# powerblade_2v0.net
KiCad netlist of a schematic drawn in EAGLE
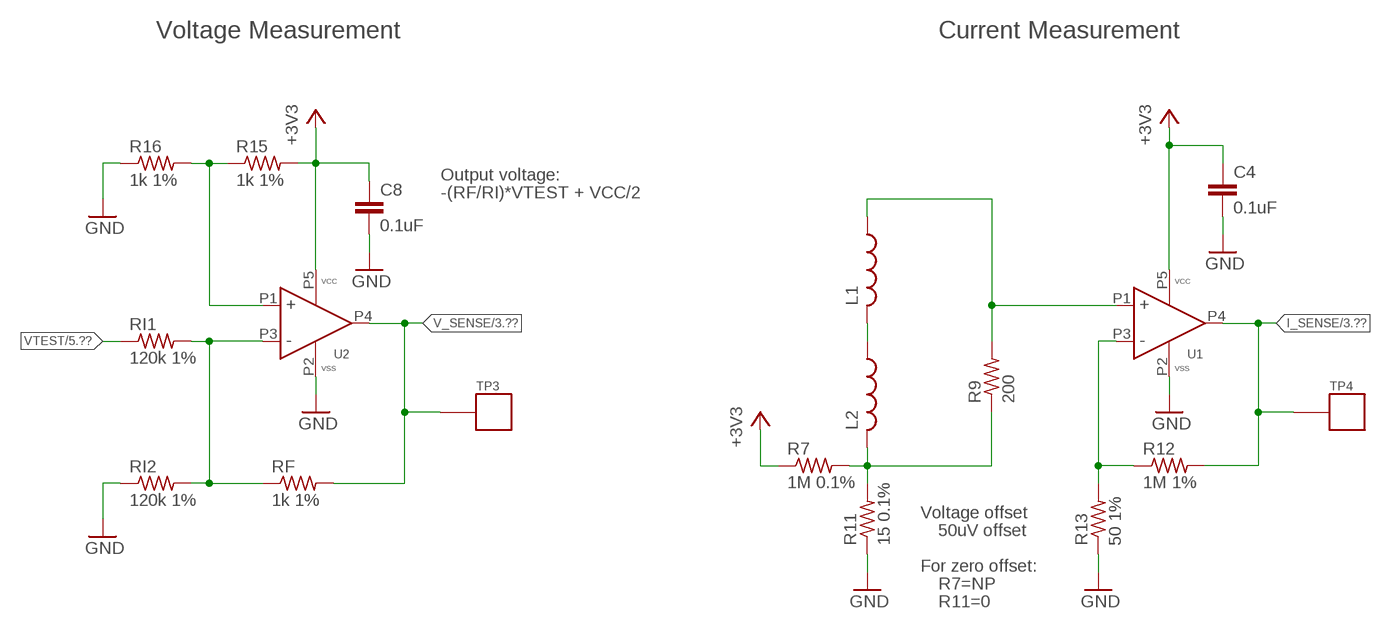
[diagram p0: schematic, sheet 1]
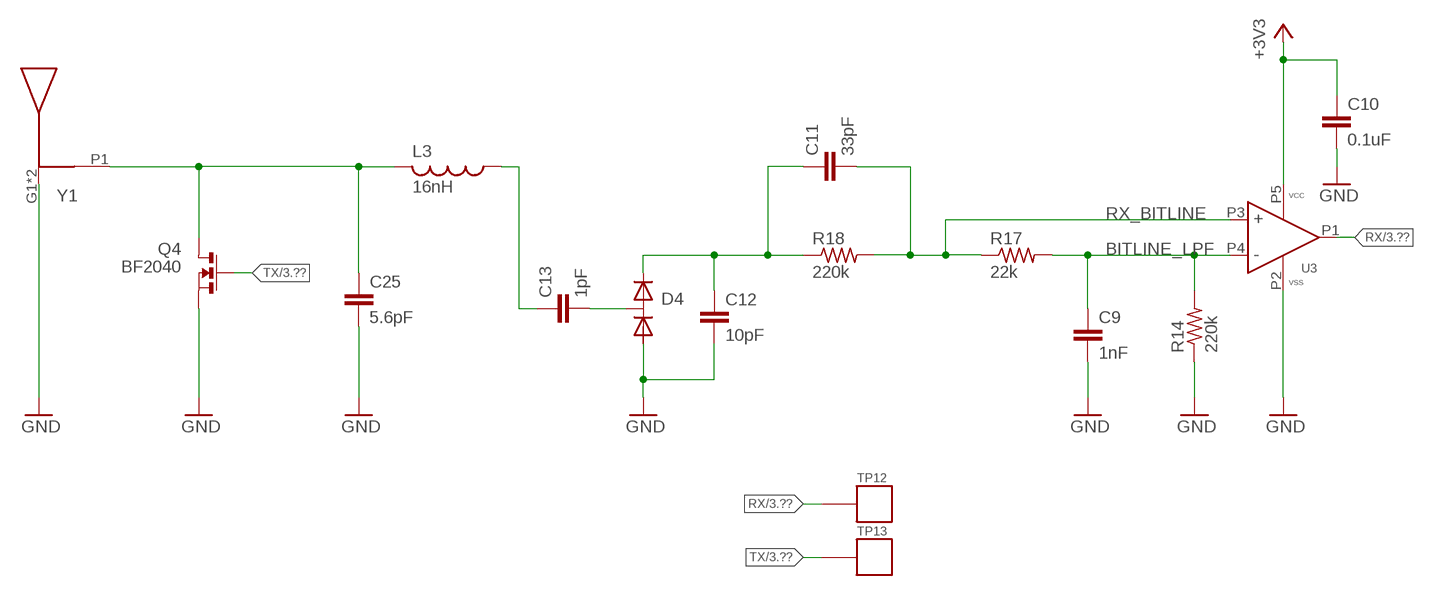
[diagram p1: schematic, sheet 2]
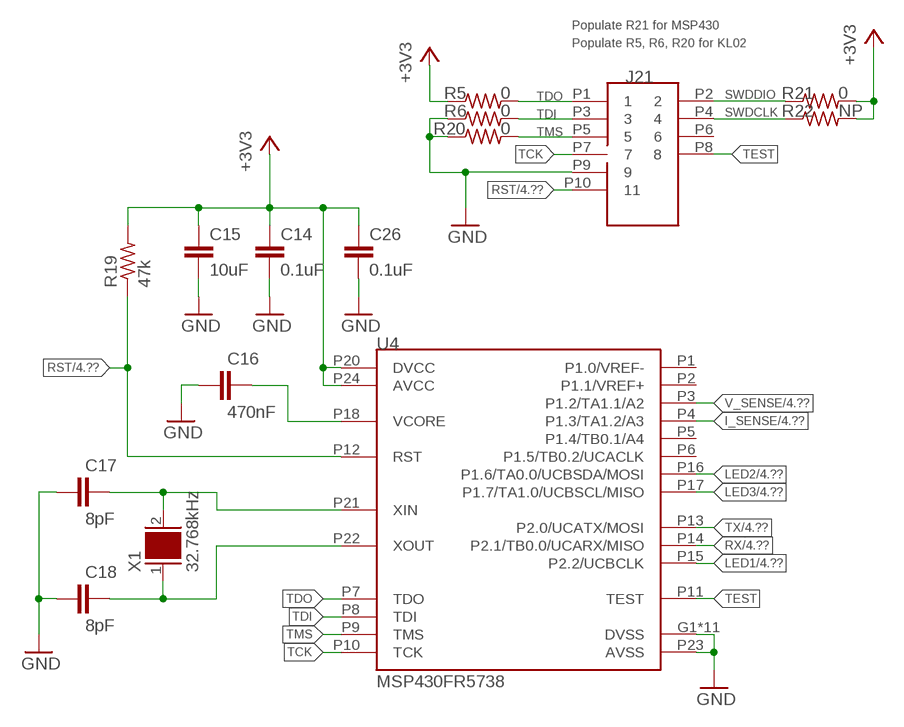
[diagram p2: schematic, sheet 3]
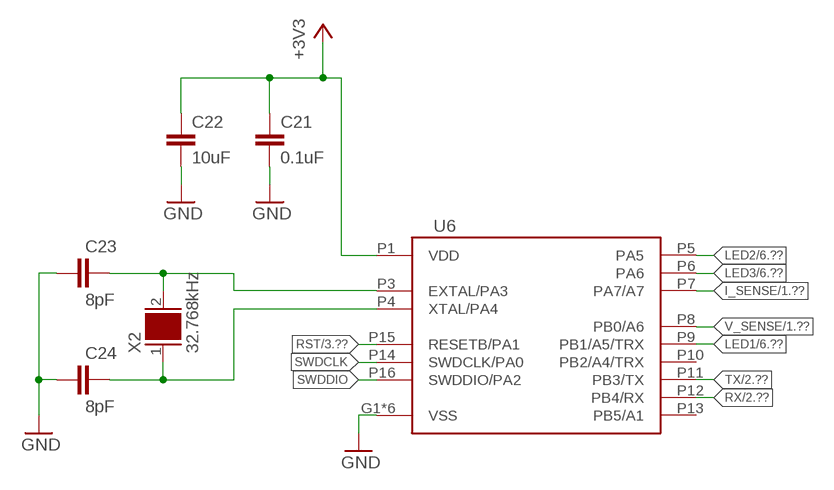
[diagram p3: schematic, sheet 4]
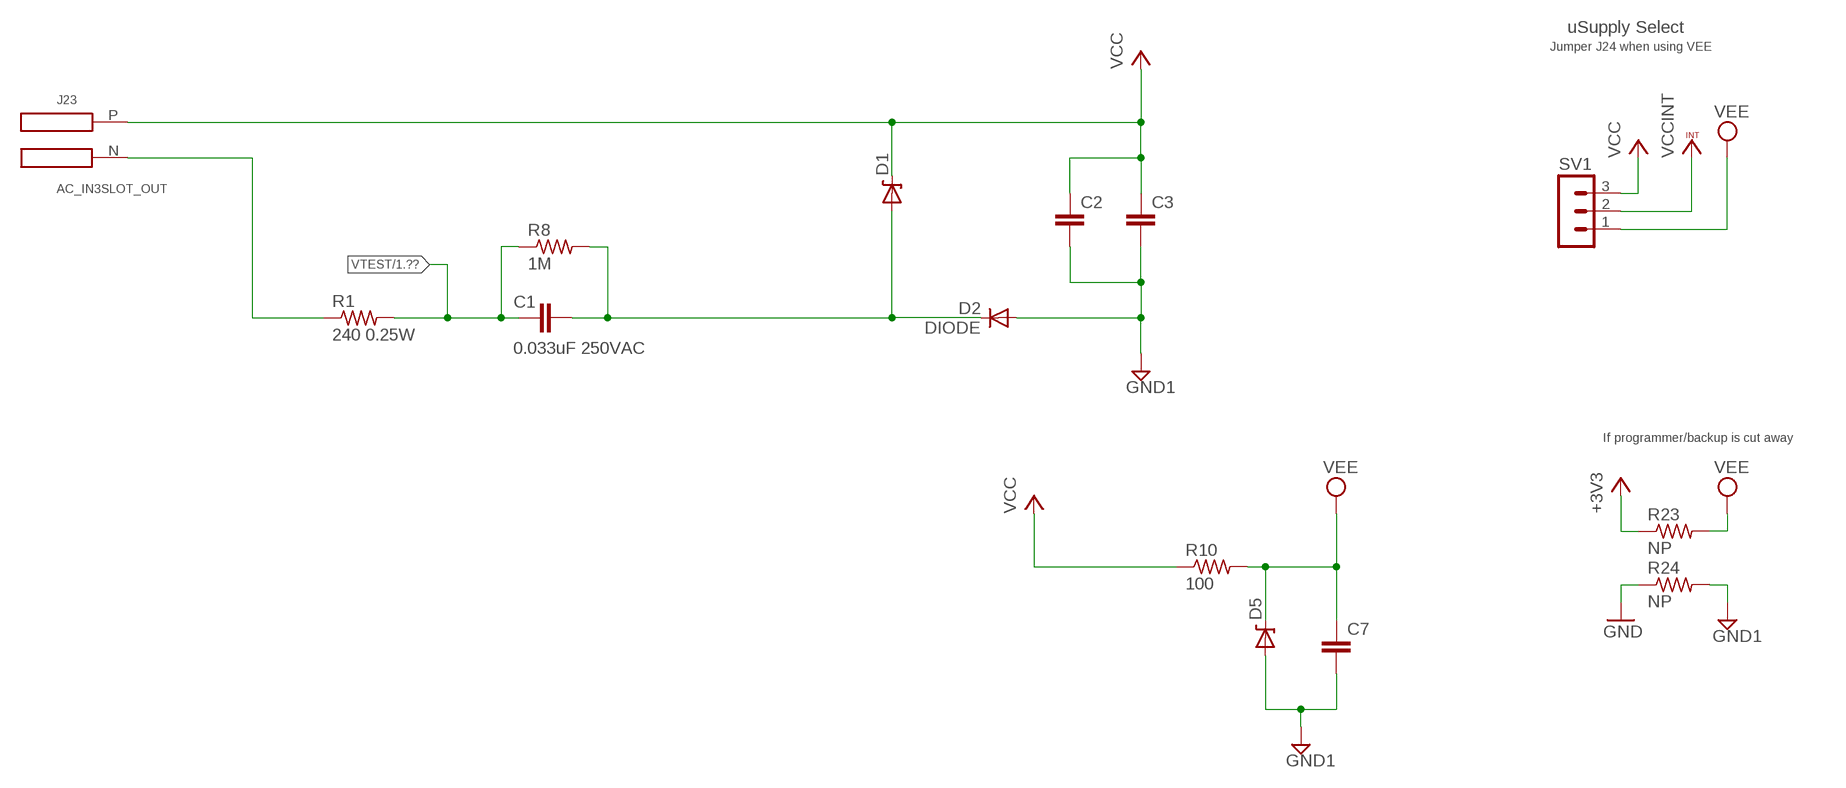
[diagram p4: schematic, sheet 5]
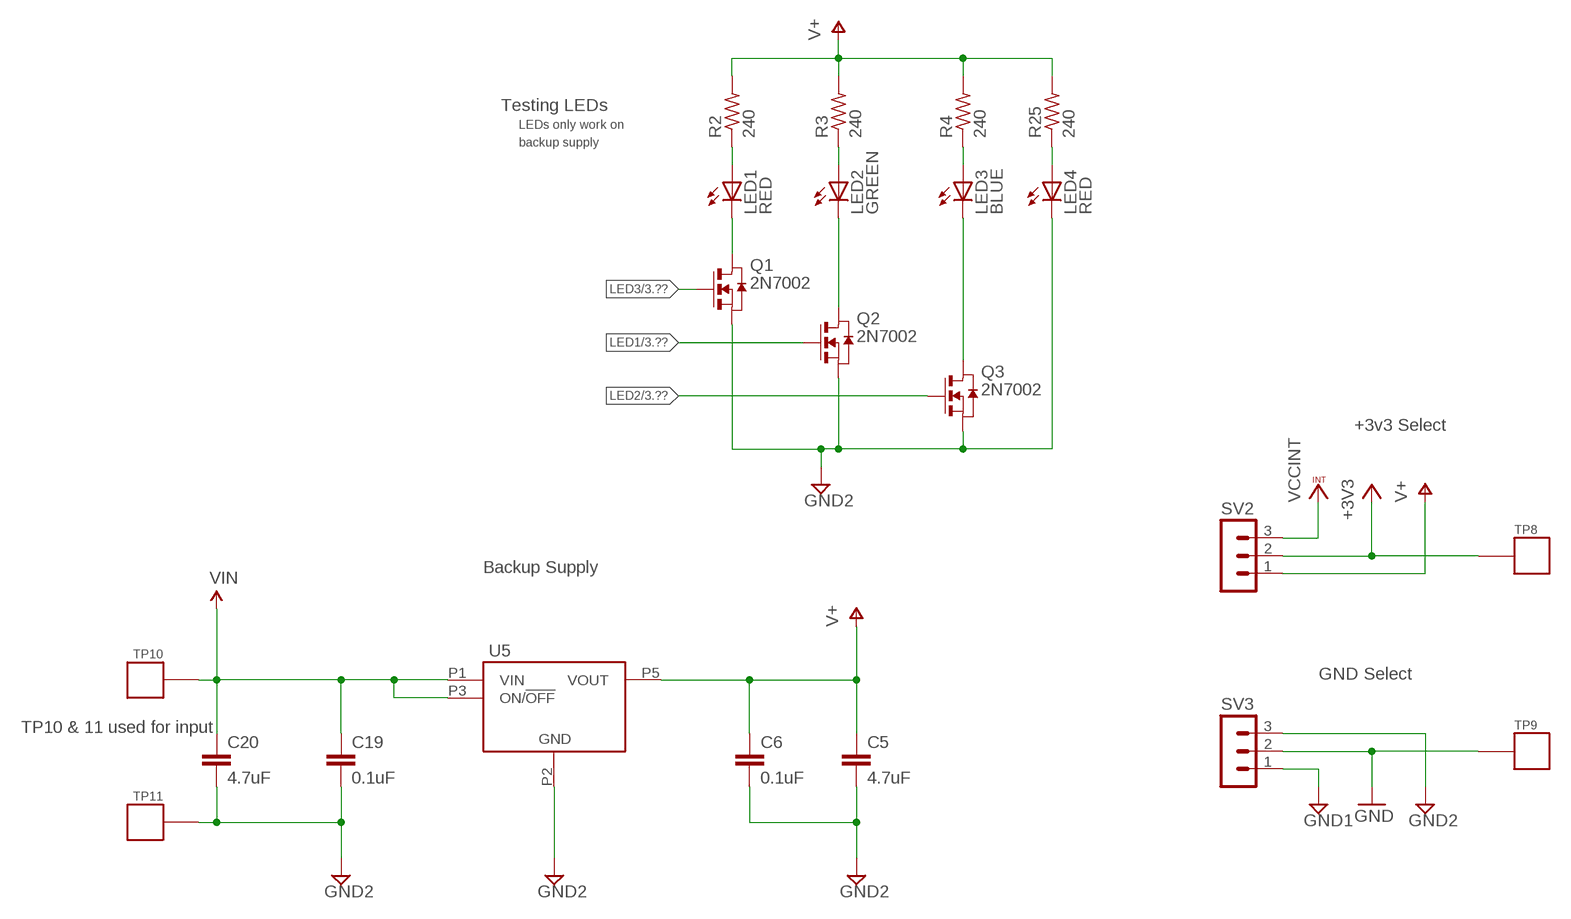
[diagram p5: schematic, sheet 6]

(export (version "E")
  (design (tool "Eeschema 10.0.6"))
  (components
    (comp (ref "C14")
      (value "0.1uF")
      (footprint "eagle-import:C0603")
      (libsource (lib "eagle-import") (part "C-EUC0603"))
    )
    (comp (ref "C15")
      (value "10uF")
      (footprint "eagle-import:C0603")
      (libsource (lib "eagle-import") (part "C-EUC0603"))
    )
    (comp (ref "C16")
      (value "470nF")
      (footprint "eagle-import:C0603")
      (libsource (lib "eagle-import") (part "C-EUC0603"))
    )
    (comp (ref "C17")
      (value "8pF")
      (footprint "eagle-import:C0603")
      (libsource (lib "eagle-import") (part "C-EUC0603"))
    )
    (comp (ref "C18")
      (value "8pF")
      (footprint "eagle-import:C0603")
      (libsource (lib "eagle-import") (part "C-EUC0603"))
    )
    (comp (ref "C26")
      (value "0.1uF")
      (footprint "eagle-import:C0603")
      (libsource (lib "eagle-import") (part "C-EUC0603"))
    )
    (comp (ref "J21")
      (value "JTAG_14PIN_IDC-NL")
      (footprint "eagle-import:TC2050-IDC-NL-430")
      (fields (field (name "TAG-CONNECT") "TC2050-IDC-NL-430"))
      (libsource (lib "eagle-import") (part "JTAG_14PIN_IDC-NL"))
    )
    (comp (ref "R5")
      (value "0")
      (footprint "eagle-import:R0603")
      (libsource (lib "eagle-import") (part "R-US_R0603"))
    )
    (comp (ref "R6")
      (value "0")
      (footprint "eagle-import:R0603")
      (libsource (lib "eagle-import") (part "R-US_R0603"))
    )
    (comp (ref "R19")
      (value "47k")
      (footprint "eagle-import:R0603")
      (libsource (lib "eagle-import") (part "R-US_R0603"))
    )
    (comp (ref "R20")
      (value "0")
      (footprint "eagle-import:R0603")
      (libsource (lib "eagle-import") (part "R-US_R0603"))
    )
    (comp (ref "R21")
      (value "0")
      (footprint "eagle-import:R0603")
      (libsource (lib "eagle-import") (part "R-US_R0603"))
    )
    (comp (ref "R22")
      (value "NP")
      (footprint "eagle-import:R0603")
      (libsource (lib "eagle-import") (part "R-US_R0603"))
    )
    (comp (ref "U4")
      (value "MSP430FR5738")
      (footprint "eagle-import:VQFN-24")
      (libsource (lib "eagle-import") (part "MSP430FR5738"))
    )
    (comp (ref "X1")
      (value "32.768kHz")
      (footprint "eagle-import:0805")
      (libsource (lib "eagle-import") (part "CRYSTAL_0805"))
    )
    (comp (ref "C1")
      (value "0.033uF 250VAC")
      (footprint "eagle-import:C2220K")
      (libsource (lib "eagle-import") (part "C-EUC2220K"))
    )
    (comp (ref "C2")
      (value "C-EUC0805")
      (footprint "eagle-import:C0805")
      (libsource (lib "eagle-import") (part "C-EUC0805"))
    )
    (comp (ref "C3")
      (value "C-EUC0603")
      (footprint "eagle-import:C0603")
      (libsource (lib "eagle-import") (part "C-EUC0603"))
    )
    (comp (ref "C7")
      (value "C-EUC0603")
      (footprint "eagle-import:C0603")
      (libsource (lib "eagle-import") (part "C-EUC0603"))
    )
    (comp (ref "D1")
      (value "ZENERBZT52")
      (footprint "eagle-import:BZT52")
      (libsource (lib "eagle-import") (part "ZENERBZT52"))
    )
    (comp (ref "D2")
      (value "DIODE")
      (footprint "eagle-import:BAS521")
      (libsource (lib "eagle-import") (part "DIODE"))
    )
    (comp (ref "D5")
      (value "ZENERBZT52")
      (footprint "eagle-import:BZT52")
      (libsource (lib "eagle-import") (part "ZENERBZT52"))
    )
    (comp (ref "J23")
      (value "AC_IN3SLOT_OUT")
      (footprint "eagle-import:AC3_SLOT_OUT")
      (libsource (lib "eagle-import") (part "AC_IN3SLOT_OUT"))
    )
    (comp (ref "R1")
      (value "240 0.25W")
      (footprint "eagle-import:R0603")
      (libsource (lib "eagle-import") (part "R-US_R0603"))
    )
    (comp (ref "R8")
      (value "1M")
      (footprint "eagle-import:R0603")
      (libsource (lib "eagle-import") (part "R-US_R0603"))
    )
    (comp (ref "R10")
      (value "100")
      (footprint "eagle-import:R0603")
      (libsource (lib "eagle-import") (part "R-US_R0603"))
    )
    (comp (ref "R23")
      (value "NP")
      (footprint "eagle-import:R0603")
      (libsource (lib "eagle-import") (part "R-US_R0603"))
    )
    (comp (ref "R24")
      (value "NP")
      (footprint "eagle-import:R0603")
      (libsource (lib "eagle-import") (part "R-US_R0603"))
    )
    (comp (ref "SV1")
      (value "MA03-1STR")
      (footprint "eagle-import:MA03-1")
      (libsource (lib "eagle-import") (part "MA03-1STR"))
    )
    (comp (ref "C9")
      (value "1nF")
      (footprint "eagle-import:C0603")
      (libsource (lib "eagle-import") (part "C-EUC0603"))
    )
    (comp (ref "C10")
      (value "0.1uF")
      (footprint "eagle-import:C0603")
      (libsource (lib "eagle-import") (part "C-EUC0603"))
    )
    (comp (ref "C11")
      (value "33pF")
      (footprint "eagle-import:C0603")
      (libsource (lib "eagle-import") (part "C-EUC0603"))
    )
    (comp (ref "C12")
      (value "10pF")
      (footprint "eagle-import:C0603")
      (libsource (lib "eagle-import") (part "C-EUC0603"))
    )
    (comp (ref "C13")
      (value "1pF")
      (footprint "eagle-import:C0603")
      (libsource (lib "eagle-import") (part "C-EUC0603"))
    )
    (comp (ref "C25")
      (value "5.6pF")
      (footprint "eagle-import:C0603")
      (libsource (lib "eagle-import") (part "C-EUC0603"))
    )
    (comp (ref "D4")
      (value "HSMS-285C")
      (footprint "eagle-import:SOT-323")
      (libsource (lib "eagle-import") (part "HSMS-285C"))
    )
    (comp (ref "L3")
      (value "16nH")
      (footprint "eagle-import:L0603")
      (libsource (lib "eagle-import") (part "L-USL0603"))
    )
    (comp (ref "Q4")
      (value "BF2040")
      (footprint "eagle-import:SOT-143")
      (libsource (lib "eagle-import") (part "BF2040"))
    )
    (comp (ref "R14")
      (value "220k")
      (footprint "eagle-import:R0603")
      (libsource (lib "eagle-import") (part "R-US_R0603"))
    )
    (comp (ref "R17")
      (value "22k")
      (footprint "eagle-import:R0603")
      (libsource (lib "eagle-import") (part "R-US_R0603"))
    )
    (comp (ref "R18")
      (value "220k")
      (footprint "eagle-import:R0603")
      (libsource (lib "eagle-import") (part "R-US_R0603"))
    )
    (comp (ref "TP12")
      (value "TP_STD")
      (footprint "eagle-import:TP")
      (libsource (lib "eagle-import") (part "TP_STD"))
    )
    (comp (ref "TP13")
      (value "TP_STD")
      (footprint "eagle-import:TP")
      (libsource (lib "eagle-import") (part "TP_STD"))
    )
    (comp (ref "U3")
      (value "NCS2200S")
      (footprint "eagle-import:SC70-5")
      (libsource (lib "eagle-import") (part "NCS2200S"))
    )
    (comp (ref "Y1")
      (value "ANT-USP")
      (footprint "eagle-import:ANT-USP")
      (fields (field (name "DIGIKEY") "ANT-916-USP-ND"))
      (libsource (lib "eagle-import") (part "ANT-USP"))
    )
    (comp (ref "C4")
      (value "0.1uF")
      (footprint "eagle-import:C0402")
      (libsource (lib "eagle-import") (part "C-EUC0402"))
    )
    (comp (ref "C8")
      (value "0.1uF")
      (footprint "eagle-import:C0402")
      (libsource (lib "eagle-import") (part "C-EUC0402"))
    )
    (comp (ref "L1")
      (value "L-USL0805")
      (footprint "eagle-import:L0805")
      (libsource (lib "eagle-import") (part "L-USL0805"))
    )
    (comp (ref "L2")
      (value "L-USL0805")
      (footprint "eagle-import:L0805")
      (libsource (lib "eagle-import") (part "L-USL0805"))
    )
    (comp (ref "R7")
      (value "1M 0.1%")
      (footprint "eagle-import:R0603")
      (libsource (lib "eagle-import") (part "R-US_R0603"))
    )
    (comp (ref "R9")
      (value "200")
      (footprint "eagle-import:R0603")
      (libsource (lib "eagle-import") (part "R-US_R0603"))
    )
    (comp (ref "R11")
      (value "15 0.1%")
      (footprint "eagle-import:R0603")
      (libsource (lib "eagle-import") (part "R-US_R0603"))
    )
    (comp (ref "R12")
      (value "1M 1%")
      (footprint "eagle-import:R0603")
      (libsource (lib "eagle-import") (part "R-US_R0603"))
    )
    (comp (ref "R13")
      (value "50 1%")
      (footprint "eagle-import:R0603")
      (libsource (lib "eagle-import") (part "R-US_R0603"))
    )
    (comp (ref "R15")
      (value "1k 1%")
      (footprint "eagle-import:R0603")
      (libsource (lib "eagle-import") (part "R-US_R0603"))
    )
    (comp (ref "R16")
      (value "1k 1%")
      (footprint "eagle-import:R0603")
      (libsource (lib "eagle-import") (part "R-US_R0603"))
    )
    (comp (ref "RF")
      (value "1k 1%")
      (footprint "eagle-import:R0603")
      (libsource (lib "eagle-import") (part "R-US_R0603"))
    )
    (comp (ref "RI1")
      (value "120k 1%")
      (footprint "eagle-import:R0603")
      (libsource (lib "eagle-import") (part "R-US_R0603"))
    )
    (comp (ref "RI2")
      (value "120k 1%")
      (footprint "eagle-import:R0603")
      (libsource (lib "eagle-import") (part "R-US_R0603"))
    )
    (comp (ref "TP3")
      (value "TP_STD")
      (footprint "eagle-import:TP")
      (libsource (lib "eagle-import") (part "TP_STD"))
    )
    (comp (ref "TP4")
      (value "TP_STD")
      (footprint "eagle-import:TP")
      (libsource (lib "eagle-import") (part "TP_STD"))
    )
    (comp (ref "U1")
      (value "MAX9910")
      (footprint "eagle-import:SC70-5")
      (libsource (lib "eagle-import") (part "MAX9910"))
    )
    (comp (ref "U2")
      (value "MAX9910")
      (footprint "eagle-import:SC70-5")
      (libsource (lib "eagle-import") (part "MAX9910"))
    )
    (comp (ref "C21")
      (value "0.1uF")
      (footprint "eagle-import:C0603")
      (libsource (lib "eagle-import") (part "C-EUC0603"))
    )
    (comp (ref "C22")
      (value "10uF")
      (footprint "eagle-import:C0603")
      (libsource (lib "eagle-import") (part "C-EUC0603"))
    )
    (comp (ref "C23")
      (value "8pF")
      (footprint "eagle-import:C0603")
      (libsource (lib "eagle-import") (part "C-EUC0603"))
    )
    (comp (ref "C24")
      (value "8pF")
      (footprint "eagle-import:C0603")
      (libsource (lib "eagle-import") (part "C-EUC0603"))
    )
    (comp (ref "U6")
      (value "KL02")
      (footprint "eagle-import:WQFN-16")
      (libsource (lib "eagle-import") (part "KL02"))
    )
    (comp (ref "X2")
      (value "32.768kHz")
      (footprint "eagle-import:0805")
      (libsource (lib "eagle-import") (part "CRYSTAL_0805"))
    )
    (comp (ref "C5")
      (value "4.7uF")
      (footprint "eagle-import:C0603")
      (libsource (lib "eagle-import") (part "C-EUC0603"))
    )
    (comp (ref "C6")
      (value "0.1uF")
      (footprint "eagle-import:C0603")
      (libsource (lib "eagle-import") (part "C-EUC0603"))
    )
    (comp (ref "C19")
      (value "0.1uF")
      (footprint "eagle-import:C0603")
      (libsource (lib "eagle-import") (part "C-EUC0603"))
    )
    (comp (ref "C20")
      (value "4.7uF")
      (footprint "eagle-import:C0603")
      (libsource (lib "eagle-import") (part "C-EUC0603"))
    )
    (comp (ref "LED1")
      (value "RED")
      (footprint "eagle-import:LED-0603")
      (libsource (lib "eagle-import") (part "LED0603"))
    )
    (comp (ref "LED2")
      (value "GREEN")
      (footprint "eagle-import:LED-0603")
      (libsource (lib "eagle-import") (part "LED0603"))
    )
    (comp (ref "LED3")
      (value "BLUE")
      (footprint "eagle-import:LED-0603")
      (libsource (lib "eagle-import") (part "LED0603"))
    )
    (comp (ref "LED4")
      (value "RED")
      (footprint "eagle-import:LED-0603")
      (libsource (lib "eagle-import") (part "LED0603"))
    )
    (comp (ref "Q1")
      (value "2N7002")
      (footprint "eagle-import:SC-70-3")
      (libsource (lib "eagle-import") (part "2N7002"))
    )
    (comp (ref "Q2")
      (value "2N7002")
      (footprint "eagle-import:SC-70-3")
      (libsource (lib "eagle-import") (part "2N7002"))
    )
    (comp (ref "Q3")
      (value "2N7002")
      (footprint "eagle-import:SC-70-3")
      (libsource (lib "eagle-import") (part "2N7002"))
    )
    (comp (ref "R2")
      (value "240")
      (footprint "eagle-import:R0603")
      (libsource (lib "eagle-import") (part "R-US_R0603"))
    )
    (comp (ref "R3")
      (value "240")
      (footprint "eagle-import:R0603")
      (libsource (lib "eagle-import") (part "R-US_R0603"))
    )
    (comp (ref "R4")
      (value "240")
      (footprint "eagle-import:R0603")
      (libsource (lib "eagle-import") (part "R-US_R0603"))
    )
    (comp (ref "R25")
      (value "240")
      (footprint "eagle-import:R0603")
      (libsource (lib "eagle-import") (part "R-US_R0603"))
    )
    (comp (ref "SV2")
      (value "MA03-1STR")
      (footprint "eagle-import:MA03-1")
      (libsource (lib "eagle-import") (part "MA03-1STR"))
    )
    (comp (ref "SV3")
      (value "MA03-1STR")
      (footprint "eagle-import:MA03-1")
      (libsource (lib "eagle-import") (part "MA03-1STR"))
    )
    (comp (ref "TP8")
      (value "TP_STD")
      (footprint "eagle-import:TP")
      (libsource (lib "eagle-import") (part "TP_STD"))
    )
    (comp (ref "TP9")
      (value "TP_STD")
      (footprint "eagle-import:TP")
      (libsource (lib "eagle-import") (part "TP_STD"))
    )
    (comp (ref "TP10")
      (value "TP_STD")
      (footprint "eagle-import:TP")
      (libsource (lib "eagle-import") (part "TP_STD"))
    )
    (comp (ref "TP11")
      (value "TP_STD")
      (footprint "eagle-import:TP")
      (libsource (lib "eagle-import") (part "TP_STD"))
    )
    (comp (ref "U5")
      (value "LP2980")
      (footprint "eagle-import:SOT-23-5")
      (libsource (lib "eagle-import") (part "LP2980"))
    )
  )
  (nets
    (net (code "1") (name "+3V3") (class "Default")
      (node (ref "C10") (pin "1") (pinfunction "1_1") (pintype "passive"))
      (node (ref "C14") (pin "1") (pinfunction "1_1") (pintype "passive"))
      (node (ref "C15") (pin "1") (pinfunction "1_1") (pintype "passive"))
      (node (ref "C21") (pin "1") (pinfunction "1_1") (pintype "passive"))
      (node (ref "C22") (pin "1") (pinfunction "1_1") (pintype "passive"))
      (node (ref "C26") (pin "1") (pinfunction "1_1") (pintype "passive"))
      (node (ref "C4") (pin "1") (pinfunction "1_1") (pintype "passive"))
      (node (ref "C8") (pin "1") (pinfunction "1_1") (pintype "passive"))
      (node (ref "R15") (pin "2") (pinfunction "2_2") (pintype "passive"))
      (node (ref "R19") (pin "2") (pinfunction "2_2") (pintype "passive"))
      (node (ref "R21") (pin "2") (pinfunction "2_2") (pintype "passive"))
      (node (ref "R22") (pin "2") (pinfunction "2_2") (pintype "passive"))
      (node (ref "R23") (pin "1") (pinfunction "1_1") (pintype "passive"))
      (node (ref "R5") (pin "1") (pinfunction "1_1") (pintype "passive"))
      (node (ref "R7") (pin "1") (pinfunction "1_1") (pintype "passive"))
      (node (ref "SV2") (pin "2") (pinfunction "2_2") (pintype "passive"))
      (node (ref "TP8") (pin "P$1") (pinfunction "P$1_P$1") (pintype "bidirectional"))
      (node (ref "U1") (pin "P5") (pinfunction "VCC_P5") (pintype "bidirectional"))
      (node (ref "U2") (pin "P5") (pinfunction "VCC_P5") (pintype "bidirectional"))
      (node (ref "U3") (pin "P5") (pinfunction "VCC_P5") (pintype "bidirectional"))
      (node (ref "U4") (pin "P20") (pinfunction "DVCC_P20") (pintype "bidirectional"))
      (node (ref "U4") (pin "P24") (pinfunction "AVCC_P24") (pintype "bidirectional"))
      (node (ref "U6") (pin "P1") (pinfunction "VDD_P1") (pintype "bidirectional"))
    )
    (net (code "2") (name "BITLINE_LPF") (class "Default")
      (node (ref "C9") (pin "1") (pinfunction "1_1") (pintype "passive"))
      (node (ref "R14") (pin "2") (pinfunction "2_2") (pintype "passive"))
      (node (ref "R17") (pin "2") (pinfunction "2_2") (pintype "passive"))
      (node (ref "U3") (pin "P4") (pinfunction "IN-_P4") (pintype "bidirectional"))
    )
    (net (code "3") (name "GND") (class "Default")
      (node (ref "C10") (pin "2") (pinfunction "2_2") (pintype "passive"))
      (node (ref "C12") (pin "2") (pinfunction "2_2") (pintype "passive"))
      (node (ref "C14") (pin "2") (pinfunction "2_2") (pintype "passive"))
      (node (ref "C15") (pin "2") (pinfunction "2_2") (pintype "passive"))
      (node (ref "C16") (pin "1") (pinfunction "1_1") (pintype "passive"))
      (node (ref "C17") (pin "1") (pinfunction "1_1") (pintype "passive"))
      (node (ref "C18") (pin "1") (pinfunction "1_1") (pintype "passive"))
      (node (ref "C21") (pin "2") (pinfunction "2_2") (pintype "passive"))
      (node (ref "C22") (pin "2") (pinfunction "2_2") (pintype "passive"))
      (node (ref "C23") (pin "1") (pinfunction "1_1") (pintype "passive"))
      (node (ref "C24") (pin "1") (pinfunction "1_1") (pintype "passive"))
      (node (ref "C25") (pin "2") (pinfunction "2_2") (pintype "passive"))
      (node (ref "C26") (pin "2") (pinfunction "2_2") (pintype "passive"))
      (node (ref "C4") (pin "2") (pinfunction "2_2") (pintype "passive"))
      (node (ref "C8") (pin "2") (pinfunction "2_2") (pintype "passive"))
      (node (ref "C9") (pin "2") (pinfunction "2_2") (pintype "passive"))
      (node (ref "D4") (pin "P1") (pinfunction "P1_P1") (pintype "passive"))
      (node (ref "J21") (pin "P9") (pinfunction "9_P9") (pintype "bidirectional"))
      (node (ref "Q4") (pin "P1") (pinfunction "S_P1") (pintype "passive"))
      (node (ref "R11") (pin "1") (pinfunction "1_1") (pintype "passive"))
      (node (ref "R13") (pin "1") (pinfunction "1_1") (pintype "passive"))
      (node (ref "R14") (pin "1") (pinfunction "1_1") (pintype "passive"))
      (node (ref "R16") (pin "1") (pinfunction "1_1") (pintype "passive"))
      (node (ref "R20") (pin "1") (pinfunction "1_1") (pintype "passive"))
      (node (ref "R24") (pin "1") (pinfunction "1_1") (pintype "passive"))
      (node (ref "R6") (pin "1") (pinfunction "1_1") (pintype "passive"))
      (node (ref "RI2") (pin "1") (pinfunction "1_1") (pintype "passive"))
      (node (ref "SV3") (pin "2") (pinfunction "2_2") (pintype "passive"))
      (node (ref "TP9") (pin "P$1") (pinfunction "P$1_P$1") (pintype "bidirectional"))
      (node (ref "U1") (pin "P2") (pinfunction "VSS_P2") (pintype "bidirectional"))
      (node (ref "U2") (pin "P2") (pinfunction "VSS_P2") (pintype "bidirectional"))
      (node (ref "U3") (pin "P2") (pinfunction "VSS_P2") (pintype "bidirectional"))
      (node (ref "U4") (pin "G1") (pinfunction "DVSS_G1") (pintype "bidirectional"))
      (node (ref "U4") (pin "G2") (pinfunction "DVSS_G2") (pintype "bidirectional"))
      (node (ref "U4") (pin "G3") (pinfunction "DVSS_G3") (pintype "bidirectional"))
      (node (ref "U4") (pin "G4") (pinfunction "DVSS_G4") (pintype "bidirectional"))
      (node (ref "U4") (pin "G5") (pinfunction "DVSS_G5") (pintype "bidirectional"))
      (node (ref "U4") (pin "G6") (pinfunction "DVSS_G6") (pintype "bidirectional"))
      (node (ref "U4") (pin "G7") (pinfunction "DVSS_G7") (pintype "bidirectional"))
      (node (ref "U4") (pin "G8") (pinfunction "DVSS_G8") (pintype "bidirectional"))
      (node (ref "U4") (pin "G9") (pinfunction "DVSS_G9") (pintype "bidirectional"))
      (node (ref "U4") (pin "P19") (pinfunction "DVSS_P19") (pintype "bidirectional"))
      (node (ref "U4") (pin "P23") (pinfunction "AVSS_P23") (pintype "bidirectional"))
      (node (ref "U4") (pin "PAD") (pinfunction "DVSS_PAD") (pintype "bidirectional"))
      (node (ref "U6") (pin "G1") (pinfunction "VSS_G1") (pintype "bidirectional"))
      (node (ref "U6") (pin "G3") (pinfunction "VSS_G3") (pintype "bidirectional"))
      (node (ref "U6") (pin "G7") (pinfunction "VSS_G7") (pintype "bidirectional"))
      (node (ref "U6") (pin "G9") (pinfunction "VSS_G9") (pintype "bidirectional"))
      (node (ref "U6") (pin "P2") (pinfunction "VSS_P2") (pintype "bidirectional"))
      (node (ref "U6") (pin "PAD") (pinfunction "VSS_PAD") (pintype "bidirectional"))
      (node (ref "Y1") (pin "G1") (pinfunction "G_G1") (pintype "bidirectional"))
      (node (ref "Y1") (pin "G2") (pinfunction "G_G2") (pintype "bidirectional"))
    )
    (net (code "4") (name "GND1") (class "Default")
      (node (ref "C2") (pin "2") (pinfunction "2_2") (pintype "passive"))
      (node (ref "C3") (pin "2") (pinfunction "2_2") (pintype "passive"))
      (node (ref "C7") (pin "2") (pinfunction "2_2") (pintype "passive"))
      (node (ref "D2") (pin "A") (pinfunction "A_A") (pintype "passive"))
      (node (ref "D5") (pin "A") (pinfunction "A_A") (pintype "passive"))
      (node (ref "R24") (pin "2") (pinfunction "2_2") (pintype "passive"))
      (node (ref "SV3") (pin "1") (pinfunction "1_1") (pintype "passive"))
    )
    (net (code "5") (name "GND2") (class "Default")
      (node (ref "C19") (pin "2") (pinfunction "2_2") (pintype "passive"))
      (node (ref "C20") (pin "2") (pinfunction "2_2") (pintype "passive"))
      (node (ref "C5") (pin "2") (pinfunction "2_2") (pintype "passive"))
      (node (ref "C6") (pin "2") (pinfunction "2_2") (pintype "passive"))
      (node (ref "LED4") (pin "C") (pinfunction "C_C") (pintype "passive"))
      (node (ref "Q1") (pin "P2") (pinfunction "S_P2") (pintype "passive"))
      (node (ref "Q2") (pin "P2") (pinfunction "S_P2") (pintype "passive"))
      (node (ref "Q3") (pin "P2") (pinfunction "S_P2") (pintype "passive"))
      (node (ref "SV3") (pin "3") (pinfunction "3_3") (pintype "passive"))
      (node (ref "TP11") (pin "P$1") (pinfunction "P$1_P$1") (pintype "bidirectional"))
      (node (ref "U5") (pin "P2") (pinfunction "GND_P2") (pintype "bidirectional"))
    )
    (net (code "6") (name "I_SENSE") (class "Default")
      (node (ref "R12") (pin "2") (pinfunction "2_2") (pintype "passive"))
      (node (ref "TP4") (pin "P$1") (pinfunction "P$1_P$1") (pintype "bidirectional"))
      (node (ref "U1") (pin "P4") (pinfunction "OUT_P4") (pintype "bidirectional"))
      (node (ref "U4") (pin "P4") (pinfunction "P1.3/TA1.2/A3_P4") (pintype "bidirectional"))
      (node (ref "U6") (pin "P7") (pinfunction "PA7/A7_P7") (pintype "bidirectional"))
    )
    (net (code "7") (name "LED1") (class "Default")
      (node (ref "Q2") (pin "P1") (pinfunction "G_P1") (pintype "passive"))
      (node (ref "U4") (pin "P15") (pinfunction "P2.2/UCBCLK_P15") (pintype "bidirectional"))
      (node (ref "U6") (pin "P9") (pinfunction "PB1/A5/TRX_P9") (pintype "bidirectional"))
    )
    (net (code "8") (name "LED2") (class "Default")
      (node (ref "Q3") (pin "P1") (pinfunction "G_P1") (pintype "passive"))
      (node (ref "U4") (pin "P16") (pinfunction "P1.6/TA0.0/UCBSDA/MOSI_P16") (pintype "bidirectional"))
      (node (ref "U6") (pin "P5") (pinfunction "PA5_P5") (pintype "bidirectional"))
    )
    (net (code "9") (name "LED3") (class "Default")
      (node (ref "Q1") (pin "P1") (pinfunction "G_P1") (pintype "passive"))
      (node (ref "U4") (pin "P17") (pinfunction "P1.7/TA1.0/UCBSCL/MISO_P17") (pintype "bidirectional"))
      (node (ref "U6") (pin "P6") (pinfunction "PA6_P6") (pintype "bidirectional"))
    )
    (net (code "10") (name "Net-(C1-Pad1)") (class "Default")
      (node (ref "C1") (pin "1") (pinfunction "1_1") (pintype "passive"))
      (node (ref "D1") (pin "A") (pinfunction "A_A") (pintype "passive"))
      (node (ref "D2") (pin "C") (pinfunction "C_C") (pintype "passive"))
      (node (ref "R8") (pin "2") (pinfunction "2_2") (pintype "passive"))
    )
    (net (code "11") (name "Net-(C11-Pad1)") (class "Default")
      (node (ref "C11") (pin "1") (pinfunction "1_1") (pintype "passive"))
      (node (ref "C12") (pin "1") (pinfunction "1_1") (pintype "passive"))
      (node (ref "D4") (pin "P2") (pinfunction "P2_P2") (pintype "passive"))
      (node (ref "R18") (pin "1") (pinfunction "1_1") (pintype "passive"))
    )
    (net (code "12") (name "Net-(C13-Pad1)") (class "Default")
      (node (ref "C13") (pin "1") (pinfunction "1_1") (pintype "passive"))
      (node (ref "L3") (pin "1") (pinfunction "1_1") (pintype "passive"))
    )
    (net (code "13") (name "Net-(C13-Pad2)") (class "Default")
      (node (ref "C13") (pin "2") (pinfunction "2_2") (pintype "passive"))
      (node (ref "D4") (pin "P3") (pinfunction "P3_P3") (pintype "passive"))
    )
    (net (code "14") (name "Net-(J23-PadN)") (class "Default")
      (node (ref "J23") (pin "N") (pinfunction "N_N") (pintype "bidirectional"))
      (node (ref "R1") (pin "1") (pinfunction "1_1") (pintype "passive"))
    )
    (net (code "15") (name "Net-(L1-Pad2)") (class "Default")
      (node (ref "L1") (pin "2") (pinfunction "2_2") (pintype "passive"))
      (node (ref "L2") (pin "1") (pinfunction "1_1") (pintype "passive"))
    )
    (net (code "16") (name "Net-(L2-Pad2)") (class "Default")
      (node (ref "L2") (pin "2") (pinfunction "2_2") (pintype "passive"))
      (node (ref "R11") (pin "2") (pinfunction "2_2") (pintype "passive"))
      (node (ref "R7") (pin "2") (pinfunction "2_2") (pintype "passive"))
      (node (ref "R9") (pin "1") (pinfunction "1_1") (pintype "passive"))
    )
    (net (code "17") (name "Net-(LED1-PadA)") (class "Default")
      (node (ref "LED1") (pin "A") (pinfunction "A_A") (pintype "passive"))
      (node (ref "R2") (pin "1") (pinfunction "1_1") (pintype "passive"))
    )
    (net (code "18") (name "Net-(LED2-PadA)") (class "Default")
      (node (ref "LED2") (pin "A") (pinfunction "A_A") (pintype "passive"))
      (node (ref "R3") (pin "1") (pinfunction "1_1") (pintype "passive"))
    )
    (net (code "19") (name "Net-(LED3-PadA)") (class "Default")
      (node (ref "LED3") (pin "A") (pinfunction "A_A") (pintype "passive"))
      (node (ref "R4") (pin "1") (pinfunction "1_1") (pintype "passive"))
    )
    (net (code "20") (name "Net-(LED4-PadA)") (class "Default")
      (node (ref "LED4") (pin "A") (pinfunction "A_A") (pintype "passive"))
      (node (ref "R25") (pin "1") (pinfunction "1_1") (pintype "passive"))
    )
    (net (code "21") (name "Net-(Q1-D)") (class "Default")
      (node (ref "LED1") (pin "C") (pinfunction "C_C") (pintype "passive"))
      (node (ref "Q1") (pin "P3") (pinfunction "D_P3") (pintype "passive"))
    )
    (net (code "22") (name "Net-(Q2-D)") (class "Default")
      (node (ref "LED2") (pin "C") (pinfunction "C_C") (pintype "passive"))
      (node (ref "Q2") (pin "P3") (pinfunction "D_P3") (pintype "passive"))
    )
    (net (code "23") (name "Net-(Q3-D)") (class "Default")
      (node (ref "LED3") (pin "C") (pinfunction "C_C") (pintype "passive"))
      (node (ref "Q3") (pin "P3") (pinfunction "D_P3") (pintype "passive"))
    )
    (net (code "24") (name "Net-(Q4-D)") (class "Default")
      (node (ref "C25") (pin "1") (pinfunction "1_1") (pintype "passive"))
      (node (ref "L3") (pin "2") (pinfunction "2_2") (pintype "passive"))
      (node (ref "Q4") (pin "P2") (pinfunction "D_P2") (pintype "passive"))
      (node (ref "Y1") (pin "P1") (pinfunction "P1_P1") (pintype "bidirectional"))
    )
    (net (code "25") (name "Net-(U1-IN+)") (class "Default")
      (node (ref "L1") (pin "1") (pinfunction "1_1") (pintype "passive"))
      (node (ref "R9") (pin "2") (pinfunction "2_2") (pintype "passive"))
      (node (ref "U1") (pin "P1") (pinfunction "IN+_P1") (pintype "bidirectional"))
    )
    (net (code "26") (name "Net-(U1-IN-)") (class "Default")
      (node (ref "R12") (pin "1") (pinfunction "1_1") (pintype "passive"))
      (node (ref "R13") (pin "2") (pinfunction "2_2") (pintype "passive"))
      (node (ref "U1") (pin "P3") (pinfunction "IN-_P3") (pintype "bidirectional"))
    )
    (net (code "27") (name "Net-(U2-IN+)") (class "Default")
      (node (ref "R15") (pin "1") (pinfunction "1_1") (pintype "passive"))
      (node (ref "R16") (pin "2") (pinfunction "2_2") (pintype "passive"))
      (node (ref "U2") (pin "P1") (pinfunction "IN+_P1") (pintype "bidirectional"))
    )
    (net (code "28") (name "Net-(U2-IN-)") (class "Default")
      (node (ref "RF") (pin "1") (pinfunction "1_1") (pintype "passive"))
      (node (ref "RI1") (pin "2") (pinfunction "2_2") (pintype "passive"))
      (node (ref "RI2") (pin "2") (pinfunction "2_2") (pintype "passive"))
      (node (ref "U2") (pin "P3") (pinfunction "IN-_P3") (pintype "bidirectional"))
    )
    (net (code "29") (name "Net-(U4-VCORE)") (class "Default")
      (node (ref "C16") (pin "2") (pinfunction "2_2") (pintype "passive"))
      (node (ref "U4") (pin "P18") (pinfunction "VCORE_P18") (pintype "bidirectional"))
    )
    (net (code "30") (name "Net-(U4-XIN)") (class "Default")
      (node (ref "C17") (pin "2") (pinfunction "2_2") (pintype "passive"))
      (node (ref "U4") (pin "P21") (pinfunction "XIN_P21") (pintype "bidirectional"))
      (node (ref "X1") (pin "2") (pinfunction "P2_2") (pintype "bidirectional"))
    )
    (net (code "31") (name "Net-(U4-XOUT)") (class "Default")
      (node (ref "C18") (pin "2") (pinfunction "2_2") (pintype "passive"))
      (node (ref "U4") (pin "P22") (pinfunction "XOUT_P22") (pintype "bidirectional"))
      (node (ref "X1") (pin "1") (pinfunction "P1_1") (pintype "bidirectional"))
    )
    (net (code "32") (name "Net-(U6-EXTAL{slash}PA3)") (class "Default")
      (node (ref "C23") (pin "2") (pinfunction "2_2") (pintype "passive"))
      (node (ref "U6") (pin "P3") (pinfunction "EXTAL/PA3_P3") (pintype "bidirectional"))
      (node (ref "X2") (pin "2") (pinfunction "P2_2") (pintype "bidirectional"))
    )
    (net (code "33") (name "Net-(U6-XTAL{slash}PA4)") (class "Default")
      (node (ref "C24") (pin "2") (pinfunction "2_2") (pintype "passive"))
      (node (ref "U6") (pin "P4") (pinfunction "XTAL/PA4_P4") (pintype "bidirectional"))
      (node (ref "X2") (pin "1") (pinfunction "P1_1") (pintype "bidirectional"))
    )
    (net (code "34") (name "RST") (class "Default")
      (node (ref "J21") (pin "P10") (pinfunction "11_P10") (pintype "bidirectional"))
      (node (ref "R19") (pin "1") (pinfunction "1_1") (pintype "passive"))
      (node (ref "U4") (pin "P12") (pinfunction "RST_P12") (pintype "bidirectional"))
      (node (ref "U6") (pin "P15") (pinfunction "RESETB/PA1_P15") (pintype "bidirectional"))
    )
    (net (code "35") (name "RX") (class "Default")
      (node (ref "TP12") (pin "P$1") (pinfunction "P$1_P$1") (pintype "bidirectional"))
      (node (ref "U3") (pin "P1") (pinfunction "OUT_P1") (pintype "bidirectional"))
      (node (ref "U4") (pin "P14") (pinfunction "P2.1/TB0.0/UCARX/MISO_P14") (pintype "bidirectional"))
      (node (ref "U6") (pin "P12") (pinfunction "PB4/RX_P12") (pintype "bidirectional"))
    )
    (net (code "36") (name "RX_BITLINE") (class "Default")
      (node (ref "C11") (pin "2") (pinfunction "2_2") (pintype "passive"))
      (node (ref "R17") (pin "1") (pinfunction "1_1") (pintype "passive"))
      (node (ref "R18") (pin "2") (pinfunction "2_2") (pintype "passive"))
      (node (ref "U3") (pin "P3") (pinfunction "IN+_P3") (pintype "bidirectional"))
    )
    (net (code "37") (name "SWDCLK") (class "Default")
      (node (ref "J21") (pin "P4") (pinfunction "4_P4") (pintype "bidirectional"))
      (node (ref "R22") (pin "1") (pinfunction "1_1") (pintype "passive"))
      (node (ref "U6") (pin "P14") (pinfunction "SWDCLK/PA0_P14") (pintype "bidirectional"))
    )
    (net (code "38") (name "SWDDIO") (class "Default")
      (node (ref "J21") (pin "P2") (pinfunction "2_P2") (pintype "bidirectional"))
      (node (ref "R21") (pin "1") (pinfunction "1_1") (pintype "passive"))
      (node (ref "U6") (pin "P16") (pinfunction "SWDDIO/PA2_P16") (pintype "bidirectional"))
    )
    (net (code "39") (name "TCK") (class "Default")
      (node (ref "J21") (pin "P7") (pinfunction "7_P7") (pintype "bidirectional"))
      (node (ref "U4") (pin "P10") (pinfunction "TCK_P10") (pintype "bidirectional"))
    )
    (net (code "40") (name "TDI") (class "Default")
      (node (ref "J21") (pin "P3") (pinfunction "3_P3") (pintype "bidirectional"))
      (node (ref "R6") (pin "2") (pinfunction "2_2") (pintype "passive"))
      (node (ref "U4") (pin "P8") (pinfunction "TDI_P8") (pintype "bidirectional"))
    )
    (net (code "41") (name "TDO") (class "Default")
      (node (ref "J21") (pin "P1") (pinfunction "1_P1") (pintype "bidirectional"))
      (node (ref "R5") (pin "2") (pinfunction "2_2") (pintype "passive"))
      (node (ref "U4") (pin "P7") (pinfunction "TDO_P7") (pintype "bidirectional"))
    )
    (net (code "42") (name "TEST") (class "Default")
      (node (ref "J21") (pin "P8") (pinfunction "8_P8") (pintype "bidirectional"))
      (node (ref "U4") (pin "P11") (pinfunction "TEST_P11") (pintype "bidirectional"))
    )
    (net (code "43") (name "TMS") (class "Default")
      (node (ref "J21") (pin "P5") (pinfunction "5_P5") (pintype "bidirectional"))
      (node (ref "R20") (pin "2") (pinfunction "2_2") (pintype "passive"))
      (node (ref "U4") (pin "P9") (pinfunction "TMS_P9") (pintype "bidirectional"))
    )
    (net (code "44") (name "TX") (class "Default")
      (node (ref "Q4") (pin "P3") (pinfunction "G_P3") (pintype "passive"))
      (node (ref "Q4") (pin "P4") (pinfunction "G_P4") (pintype "passive"))
      (node (ref "TP13") (pin "P$1") (pinfunction "P$1_P$1") (pintype "bidirectional"))
      (node (ref "U4") (pin "P13") (pinfunction "P2.0/UCATX/MOSI_P13") (pintype "bidirectional"))
      (node (ref "U6") (pin "P11") (pinfunction "PB3/TX_P11") (pintype "bidirectional"))
    )
    (net (code "45") (name "V+") (class "Default")
      (node (ref "C5") (pin "1") (pinfunction "1_1") (pintype "passive"))
      (node (ref "C6") (pin "1") (pinfunction "1_1") (pintype "passive"))
      (node (ref "R2") (pin "2") (pinfunction "2_2") (pintype "passive"))
      (node (ref "R25") (pin "2") (pinfunction "2_2") (pintype "passive"))
      (node (ref "R3") (pin "2") (pinfunction "2_2") (pintype "passive"))
      (node (ref "R4") (pin "2") (pinfunction "2_2") (pintype "passive"))
      (node (ref "SV2") (pin "1") (pinfunction "1_1") (pintype "passive"))
      (node (ref "U5") (pin "P5") (pinfunction "VOUT_P5") (pintype "bidirectional"))
    )
    (net (code "46") (name "VCC") (class "Default")
      (node (ref "C2") (pin "1") (pinfunction "1_1") (pintype "passive"))
      (node (ref "C3") (pin "1") (pinfunction "1_1") (pintype "passive"))
      (node (ref "D1") (pin "C") (pinfunction "C_C") (pintype "passive"))
      (node (ref "J23") (pin "P") (pinfunction "P_P") (pintype "bidirectional"))
      (node (ref "R10") (pin "1") (pinfunction "1_1") (pintype "passive"))
      (node (ref "SV1") (pin "3") (pinfunction "3_3") (pintype "passive"))
    )
    (net (code "47") (name "VCCINT") (class "Default")
      (node (ref "SV1") (pin "2") (pinfunction "2_2") (pintype "passive"))
      (node (ref "SV2") (pin "3") (pinfunction "3_3") (pintype "passive"))
    )
    (net (code "48") (name "VEE") (class "Default")
      (node (ref "C7") (pin "1") (pinfunction "1_1") (pintype "passive"))
      (node (ref "D5") (pin "C") (pinfunction "C_C") (pintype "passive"))
      (node (ref "R10") (pin "2") (pinfunction "2_2") (pintype "passive"))
      (node (ref "R23") (pin "2") (pinfunction "2_2") (pintype "passive"))
      (node (ref "SV1") (pin "1") (pinfunction "1_1") (pintype "passive"))
    )
    (net (code "49") (name "VIN") (class "Default")
      (node (ref "C19") (pin "1") (pinfunction "1_1") (pintype "passive"))
      (node (ref "C20") (pin "1") (pinfunction "1_1") (pintype "passive"))
      (node (ref "TP10") (pin "P$1") (pinfunction "P$1_P$1") (pintype "bidirectional"))
      (node (ref "U5") (pin "P1") (pinfunction "VIN_P1") (pintype "bidirectional"))
      (node (ref "U5") (pin "P3") (pinfunction "ON/~{OFF}_P3") (pintype "bidirectional"))
    )
    (net (code "50") (name "VTEST") (class "Default")
      (node (ref "C1") (pin "2") (pinfunction "2_2") (pintype "passive"))
      (node (ref "R1") (pin "2") (pinfunction "2_2") (pintype "passive"))
      (node (ref "R8") (pin "1") (pinfunction "1_1") (pintype "passive"))
      (node (ref "RI1") (pin "1") (pinfunction "1_1") (pintype "passive"))
    )
    (net (code "51") (name "V_SENSE") (class "Default")
      (node (ref "RF") (pin "2") (pinfunction "2_2") (pintype "passive"))
      (node (ref "TP3") (pin "P$1") (pinfunction "P$1_P$1") (pintype "bidirectional"))
      (node (ref "U2") (pin "P4") (pinfunction "OUT_P4") (pintype "bidirectional"))
      (node (ref "U4") (pin "P3") (pinfunction "P1.2/TA1.1/A2_P3") (pintype "bidirectional"))
      (node (ref "U6") (pin "P8") (pinfunction "PB0/A6_P8") (pintype "bidirectional"))
    )
    (net (code "52") (name "unconnected-(J21-6-PadP6)") (class "Default")
      (node (ref "J21") (pin "P6") (pinfunction "6_P6") (pintype "bidirectional"))
    )
    (net (code "53") (name "unconnected-(U4-P1.0{slash}VREF--PadP1)") (class "Default")
      (node (ref "U4") (pin "P1") (pinfunction "P1.0/VREF-_P1") (pintype "bidirectional"))
    )
    (net (code "54") (name "unconnected-(U4-P1.1{slash}VREF+-PadP2)") (class "Default")
      (node (ref "U4") (pin "P2") (pinfunction "P1.1/VREF+_P2") (pintype "bidirectional"))
    )
    (net (code "55") (name "unconnected-(U4-P1.4{slash}TB0.1{slash}A4-PadP5)") (class "Default")
      (node (ref "U4") (pin "P5") (pinfunction "P1.4/TB0.1/A4_P5") (pintype "bidirectional"))
    )
    (net (code "56") (name "unconnected-(U4-P1.5{slash}TB0.2{slash}UCACLK-PadP6)") (class "Default")
      (node (ref "U4") (pin "P6") (pinfunction "P1.5/TB0.2/UCACLK_P6") (pintype "bidirectional"))
    )
    (net (code "57") (name "unconnected-(U6-PB2{slash}A4{slash}TRX-PadP10)") (class "Default")
      (node (ref "U6") (pin "P10") (pinfunction "PB2/A4/TRX_P10") (pintype "bidirectional"))
    )
    (net (code "58") (name "unconnected-(U6-PB5{slash}A1-PadP13)") (class "Default")
      (node (ref "U6") (pin "P13") (pinfunction "PB5/A1_P13") (pintype "bidirectional"))
    )
  )
)
